# schematic_sheet1.net
KiCad netlist of a schematic drawn in Altium Designer
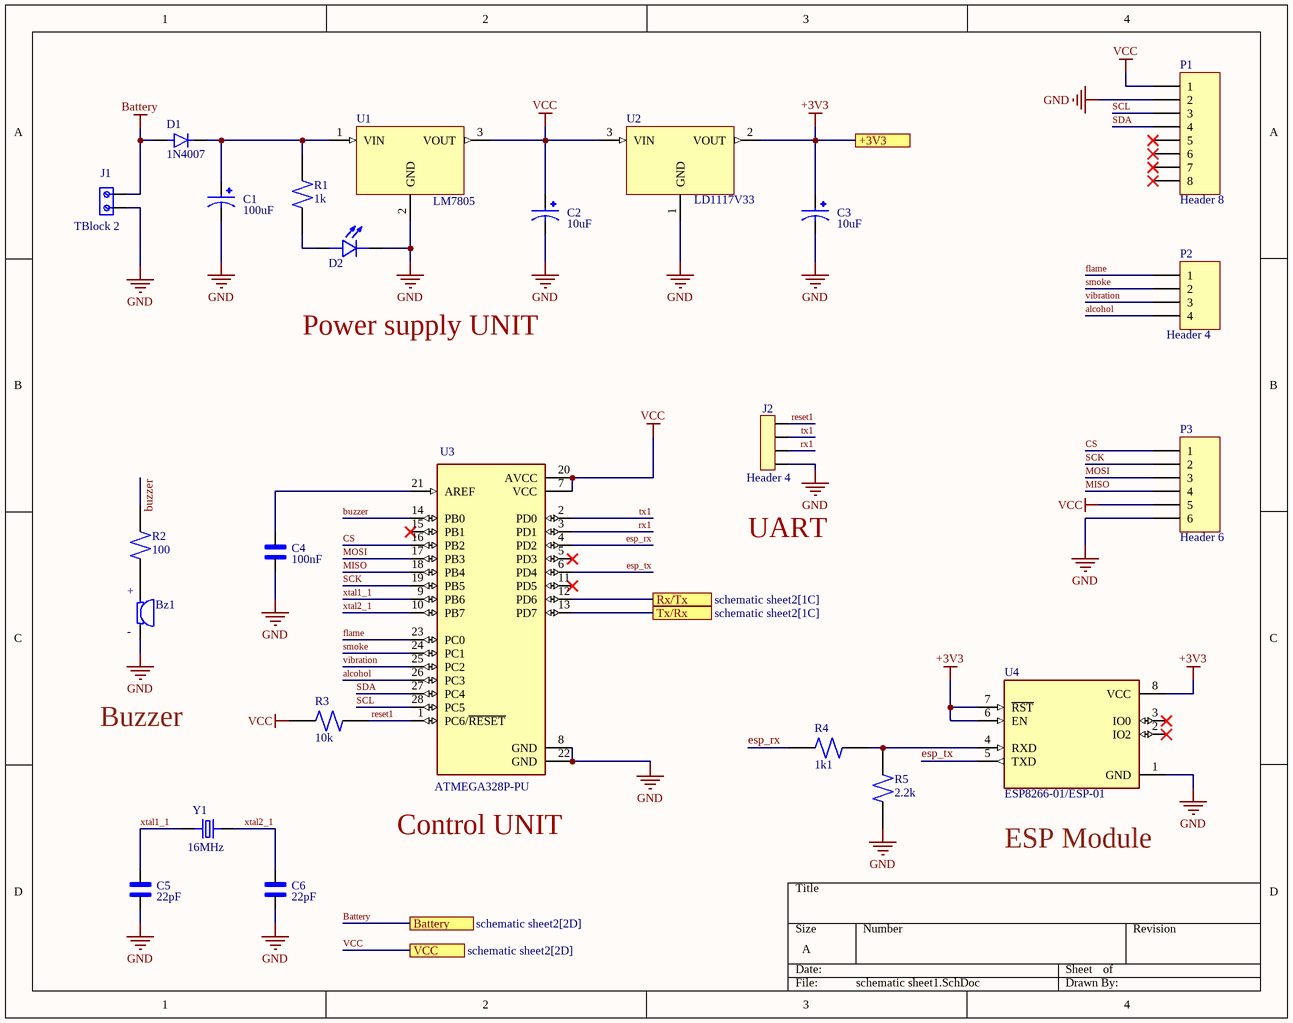
[diagram p0: schematic sheet1.SchDoc]

(export (version "E")
  (design (tool "Eeschema 10.0.6"))
  (components
    (comp (ref "Bz1")
      (value "AI-1223-TWT-12V-R")
      (footprint "XDCR_AI-1223-TWT-12V-R")
      (description "ELECTRO-MECHANICAL AUDIO INDICATOR")
      (fields (field (name "MF") "PUI Audio,"))
      (libsource (lib "Installed library") (part "Buzzer"))
    )
    (comp (ref "C1")
      (value "100uF")
      (footprint "CAPPRD500W50D500H1100")
      (description "FS-A")
      (fields (field (name "MF") "{'manufacturer': u'Panasonic'}") (field (name "MP") "EEUFS0J221B"))
      (libsource (lib "Installed library") (part "Electrolytic capacitor"))
    )
    (comp (ref "C2")
      (value "10uF")
      (footprint "CAPPRD500W50D500H1100")
      (description "FS-A")
      (fields (field (name "MF") "{'manufacturer': u'Panasonic'}") (field (name "MP") "EEUFS0J221B"))
      (libsource (lib "Installed library") (part "Electrolytic capacitor"))
    )
    (comp (ref "C3")
      (value "10uF")
      (footprint "CAPPRD500W50D500H1100")
      (description "FS-A")
      (fields (field (name "MF") "{'manufacturer': u'Panasonic'}") (field (name "MP") "EEUFS0J221B"))
      (libsource (lib "Installed library") (part "Electrolytic capacitor"))
    )
    (comp (ref "C4")
      (value "100nF")
      (footprint "CAPRB500W50L450T300H550")
      (description "2200 pF Â±10% 250V Ceramic Capacitor X7R Radial")
      (fields (field (name "DIGI-KEY_PART_NUMBER") "445-173386-1-ND") (field (name "MF") "TDK"))
      (libsource (lib "Installed library") (part "Ceramic capacitor"))
    )
    (comp (ref "C5")
      (value "22pF")
      (footprint "CAPRB500W50L450T300H550")
      (description "2200 pF Â±10% 250V Ceramic Capacitor X7R Radial")
      (fields (field (name "DIGI-KEY_PART_NUMBER") "445-173386-1-ND") (field (name "MF") "TDK"))
      (libsource (lib "Installed library") (part "Ceramic capacitor"))
    )
    (comp (ref "C6")
      (value "22pF")
      (footprint "CAPRB500W50L450T300H550")
      (description "2200 pF Â±10% 250V Ceramic Capacitor X7R Radial")
      (fields (field (name "DIGI-KEY_PART_NUMBER") "445-173386-1-ND") (field (name "MF") "TDK"))
      (libsource (lib "Installed library") (part "Ceramic capacitor"))
    )
    (comp (ref "D1")
      (value "1N4007")
      (footprint "DIOAD1060W80L520D270")
      (description "Diode Switching 1KV 1A 2-Pin DO-41")
      (libsource (lib "Components") (part "1N4007"))
    )
    (comp (ref "D2")
      (value "L08R5000Q1")
      (footprint "LEDRD254W57D500H1070")
      (description "LED, Orange, Through Hole, T-1 3/4 (5mm), 30 mA, 2.1 V, 635 nm")
      (fields (field (name "MF") "{'manufacturer': u'LED Technology'}"))
      (libsource (lib "Installed library") (part "LED"))
    )
    (comp (ref "J1")
      (value "TBlock 2")
      (footprint "691111710002")
      (description "2 Position Wire to Board Terminal Block Horizontal with Board 0.197 _5.00mm_ Through Hole")
      (fields (field (name "MP") "691111710002") (field (name "MF") "Wurth Electronics"))
      (libsource (lib "Installed library") (part "Terminal Block - 2Pins"))
    )
    (comp (ref "J2")
      (value "Header 4")
      (footprint "SULLINS_PPTC041LFBN-RC")
      (description "4 Position Header Connector Through Hole")
      (fields (field (name "MP") "PPTC041LFBN-RC") (field (name "MF") "Sullins Connector"))
      (libsource (lib "Installed library") (part "Female header - 4Pins"))
    )
    (comp (ref "P1")
      (value "Header 8")
      (footprint "HDR1X8")
      (description "Header, 8-Pin")
      (fields (field (name "PUBLISHER") "Altium Limited"))
      (libsource (lib "Miscellaneous Connectors") (part "Header 8"))
    )
    (comp (ref "P2")
      (value "Header 4")
      (footprint "HDR1X4")
      (description "Header, 4-Pin")
      (fields (field (name "PUBLISHER") "Altium Limited"))
      (libsource (lib "Miscellaneous Connectors") (part "Header 4"))
    )
    (comp (ref "P3")
      (value "Header 6")
      (footprint "HDR1X6")
      (description "Header, 6-Pin")
      (fields (field (name "PUBLISHER") "Altium Limited"))
      (libsource (lib "Miscellaneous Connectors") (part "Header 6"))
    )
    (comp (ref "R1")
      (value "1k")
      (footprint "RESAD1100W55L680D260")
      (description "(MFR-25FBF52-10K) 10,2 kOhm bei 1% 0,25W, 1/4W Durchbohrlochwiderstand Axial Metal Film")
      (fields (field (name "DIGI-KEY_PART_NUMBER") "10.2KXBK-ND") (field (name "MF") "Yageo"))
      (libsource (lib "Installed library") (part "Resistor (0.25W)"))
    )
    (comp (ref "R2")
      (value "100")
      (footprint "RESAD1100W55L680D260")
      (description "(MFR-25FBF52-10K) 10,2 kOhm bei 1% 0,25W, 1/4W Durchbohrlochwiderstand Axial Metal Film")
      (fields (field (name "DIGI-KEY_PART_NUMBER") "10.2KXBK-ND") (field (name "MF") "Yageo"))
      (libsource (lib "Installed library") (part "Resistor (0.25W)"))
    )
    (comp (ref "R3")
      (value "10k")
      (footprint "RESAD1100W55L680D260")
      (description "(MFR-25FBF52-10K) 10,2 kOhm bei 1% 0,25W, 1/4W Durchbohrlochwiderstand Axial Metal Film")
      (fields (field (name "DIGI-KEY_PART_NUMBER") "10.2KXBK-ND") (field (name "MF") "Yageo"))
      (libsource (lib "Installed library") (part "Resistor (0.25W)"))
    )
    (comp (ref "R4")
      (value "1k1")
      (footprint "RESAD1100W55L680D260")
      (description "(MFR-25FBF52-10K) 10,2 kOhm bei 1% 0,25W, 1/4W Durchbohrlochwiderstand Axial Metal Film")
      (fields (field (name "DIGI-KEY_PART_NUMBER") "10.2KXBK-ND") (field (name "MF") "Yageo"))
      (libsource (lib "Installed library") (part "Resistor (0.25W)"))
    )
    (comp (ref "R5")
      (value "2.2k")
      (footprint "RESAD1100W55L680D260")
      (description "(MFR-25FBF52-10K) 10,2 kOhm bei 1% 0,25W, 1/4W Durchbohrlochwiderstand Axial Metal Film")
      (fields (field (name "DIGI-KEY_PART_NUMBER") "10.2KXBK-ND") (field (name "MF") "Yageo"))
      (libsource (lib "Installed library") (part "Resistor (0.25W)"))
    )
    (comp (ref "U1")
      (value "LM7805")
      (footprint "TO255P1020X450X1968-3")
      (fields (field (name "MP") "LM7805CT/NOPB"))
      (libsource (lib "Voltage regulator") (part "LM78__"))
    )
    (comp (ref "U2")
      (value "LD1117V33")
      (footprint "TO255P1020X450X1968-3")
      (libsource (lib "Voltage regulator") (part "LD1117V33"))
    )
    (comp (ref "U3")
      (value "ATMEGA328P-PU")
      (footprint "DIP794W46P254L2967H457Q28B")
      (description "ATmega Series 20 MHz 32 KB Flash 2 KB SRAM 8-Bit Microcontroller - DIP-28")
      (libsource (lib "Installed library") (part "ATMEGA328P-PU"))
    )
    (comp (ref "U4")
      (value "ESP8266-01/ESP-01")
      (footprint "XCVR_ESP8266-01/ESP-01")
      (libsource (lib "Installed library") (part "ESP8266-01 Module"))
    )
    (comp (ref "Y1")
      (value "16MHz")
      (footprint "XTAL_ECS-160-20-4X")
      (description "CRYSTAL T/H")
      (fields (field (name "MF") "{'manufacturer': u'ECS Inc.'}") (field (name "MP") "ECS-160-S-4"))
      (libsource (lib "Installed library") (part "Crystal oscilator"))
    )
  )
  (nets
    (net (code "1") (name "+3V3") (class "Default")
      (node (ref "C3") (pin "P") (pinfunction "P_P") (pintype "passive"))
      (node (ref "U2") (pin "2") (pinfunction "VOUT_2") (pintype "output"))
      (node (ref "U4") (pin "6") (pinfunction "EN_6") (pintype "input"))
      (node (ref "U4") (pin "7") (pinfunction "~{RST}_7") (pintype "input"))
      (node (ref "U4") (pin "8") (pinfunction "VCC_8") (pintype "power_in"))
    )
    (net (code "2") (name "/CS") (class "Default")
      (node (ref "P3") (pin "1") (pinfunction "1_1") (pintype "passive"))
      (node (ref "U3") (pin "16") (pinfunction "PB2_16") (pintype "bidirectional"))
    )
    (net (code "3") (name "/MISO") (class "Default")
      (node (ref "P3") (pin "4") (pinfunction "4_4") (pintype "passive"))
      (node (ref "U3") (pin "18") (pinfunction "PB4_18") (pintype "bidirectional"))
    )
    (net (code "4") (name "/MOSI") (class "Default")
      (node (ref "P3") (pin "3") (pinfunction "3_3") (pintype "passive"))
      (node (ref "U3") (pin "17") (pinfunction "PB3_17") (pintype "bidirectional"))
    )
    (net (code "5") (name "/Rx{slash}Tx") (class "Default")
      (node (ref "U3") (pin "12") (pinfunction "PD6_12") (pintype "bidirectional"))
    )
    (net (code "6") (name "/SCK") (class "Default")
      (node (ref "P3") (pin "2") (pinfunction "2_2") (pintype "passive"))
      (node (ref "U3") (pin "19") (pinfunction "PB5_19") (pintype "bidirectional"))
    )
    (net (code "7") (name "/SCL") (class "Default")
      (node (ref "P1") (pin "3") (pinfunction "3_3") (pintype "passive"))
      (node (ref "U3") (pin "28") (pinfunction "PC5_28") (pintype "bidirectional"))
    )
    (net (code "8") (name "/SDA") (class "Default")
      (node (ref "P1") (pin "4") (pinfunction "4_4") (pintype "passive"))
      (node (ref "U3") (pin "27") (pinfunction "PC4_27") (pintype "bidirectional"))
    )
    (net (code "9") (name "/Tx{slash}Rx") (class "Default")
      (node (ref "U3") (pin "13") (pinfunction "PD7_13") (pintype "bidirectional"))
    )
    (net (code "10") (name "/alcohol") (class "Default")
      (node (ref "P2") (pin "4") (pinfunction "4_4") (pintype "passive"))
      (node (ref "U3") (pin "26") (pinfunction "PC3_26") (pintype "bidirectional"))
    )
    (net (code "11") (name "/buzzer") (class "Default")
      (node (ref "R2") (pin "2") (pinfunction "2_2") (pintype "passive"))
      (node (ref "U3") (pin "14") (pinfunction "PB0_14") (pintype "bidirectional"))
    )
    (net (code "12") (name "/esp_rx") (class "Default")
      (node (ref "R4") (pin "2") (pinfunction "2_2") (pintype "passive"))
      (node (ref "U3") (pin "4") (pinfunction "PD2_4") (pintype "bidirectional"))
    )
    (net (code "13") (name "/esp_tx") (class "Default")
      (node (ref "U3") (pin "6") (pinfunction "PD4_6") (pintype "bidirectional"))
      (node (ref "U4") (pin "5") (pinfunction "TXD_5") (pintype "output"))
    )
    (net (code "14") (name "/flame") (class "Default")
      (node (ref "P2") (pin "1") (pinfunction "1_1") (pintype "passive"))
      (node (ref "U3") (pin "23") (pinfunction "PC0_23") (pintype "bidirectional"))
    )
    (net (code "15") (name "/reset1") (class "Default")
      (node (ref "J2") (pin "1") (pinfunction "1_1") (pintype "passive"))
      (node (ref "R3") (pin "2") (pinfunction "2_2") (pintype "passive"))
      (node (ref "U3") (pin "1") (pinfunction "PC6/~{RESET}_1") (pintype "bidirectional"))
    )
    (net (code "16") (name "/rx1") (class "Default")
      (node (ref "J2") (pin "3") (pinfunction "3_3") (pintype "passive"))
      (node (ref "U3") (pin "3") (pinfunction "PD1_3") (pintype "bidirectional"))
    )
    (net (code "17") (name "/smoke") (class "Default")
      (node (ref "P2") (pin "2") (pinfunction "2_2") (pintype "passive"))
      (node (ref "U3") (pin "24") (pinfunction "PC1_24") (pintype "bidirectional"))
    )
    (net (code "18") (name "/tx1") (class "Default")
      (node (ref "J2") (pin "2") (pinfunction "2_2") (pintype "passive"))
      (node (ref "U3") (pin "2") (pinfunction "PD0_2") (pintype "bidirectional"))
    )
    (net (code "19") (name "/vibration") (class "Default")
      (node (ref "P2") (pin "3") (pinfunction "3_3") (pintype "passive"))
      (node (ref "U3") (pin "25") (pinfunction "PC2_25") (pintype "bidirectional"))
    )
    (net (code "20") (name "/xtal1_1") (class "Default")
      (node (ref "C5") (pin "1") (pinfunction "1_1") (pintype "passive"))
      (node (ref "U3") (pin "9") (pinfunction "PB6_9") (pintype "bidirectional"))
      (node (ref "Y1") (pin "1") (pinfunction "1_1") (pintype "passive"))
    )
    (net (code "21") (name "/xtal2_1") (class "Default")
      (node (ref "C6") (pin "1") (pinfunction "1_1") (pintype "passive"))
      (node (ref "U3") (pin "10") (pinfunction "PB7_10") (pintype "bidirectional"))
      (node (ref "Y1") (pin "2") (pinfunction "2_2") (pintype "passive"))
    )
    (net (code "22") (name "Battery") (class "Default")
      (node (ref "D1") (pin "A") (pinfunction "A_A") (pintype "passive"))
      (node (ref "J1") (pin "2") (pinfunction "2_2") (pintype "passive"))
    )
    (net (code "23") (name "GND") (class "Default")
      (node (ref "Bz1") (pin "N") (pinfunction "NEG_N") (pintype "passive"))
      (node (ref "C1") (pin "N") (pinfunction "N_N") (pintype "passive"))
      (node (ref "C2") (pin "N") (pinfunction "N_N") (pintype "passive"))
      (node (ref "C3") (pin "N") (pinfunction "N_N") (pintype "passive"))
      (node (ref "C4") (pin "2") (pinfunction "2_2") (pintype "passive"))
      (node (ref "C5") (pin "2") (pinfunction "2_2") (pintype "passive"))
      (node (ref "C6") (pin "2") (pinfunction "2_2") (pintype "passive"))
      (node (ref "D2") (pin "C") (pinfunction "C_C") (pintype "passive"))
      (node (ref "J1") (pin "1") (pinfunction "1_1") (pintype "passive"))
      (node (ref "J2") (pin "4") (pinfunction "4_4") (pintype "passive"))
      (node (ref "P1") (pin "2") (pinfunction "2_2") (pintype "passive"))
      (node (ref "P3") (pin "6") (pinfunction "6_6") (pintype "passive"))
      (node (ref "R5") (pin "1") (pinfunction "1_1") (pintype "passive"))
      (node (ref "U1") (pin "2") (pinfunction "GND_2") (pintype "passive"))
      (node (ref "U2") (pin "1") (pinfunction "GND_1") (pintype "passive"))
      (node (ref "U3") (pin "22") (pinfunction "GND_22") (pintype "power_in"))
      (node (ref "U3") (pin "8") (pinfunction "GND_8") (pintype "power_in"))
      (node (ref "U4") (pin "1") (pinfunction "GND_1") (pintype "power_in"))
    )
    (net (code "24") (name "Net-(Bz1-POS)") (class "Default")
      (node (ref "Bz1") (pin "P") (pinfunction "POS_P") (pintype "passive"))
      (node (ref "R2") (pin "1") (pinfunction "1_1") (pintype "passive"))
    )
    (net (code "25") (name "Net-(D2-PadA)") (class "Default")
      (node (ref "D2") (pin "A") (pinfunction "A_A") (pintype "passive"))
      (node (ref "R1") (pin "2") (pinfunction "2_2") (pintype "passive"))
    )
    (net (code "26") (name "Net-(U1-VIN)") (class "Default")
      (node (ref "C1") (pin "P") (pinfunction "P_P") (pintype "passive"))
      (node (ref "D1") (pin "C") (pinfunction "C_C") (pintype "passive"))
      (node (ref "R1") (pin "1") (pinfunction "1_1") (pintype "passive"))
      (node (ref "U1") (pin "1") (pinfunction "VIN_1") (pintype "input"))
    )
    (net (code "27") (name "Net-(U3-AREF)") (class "Default")
      (node (ref "C4") (pin "1") (pinfunction "1_1") (pintype "passive"))
      (node (ref "U3") (pin "21") (pinfunction "AREF_21") (pintype "input"))
    )
    (net (code "28") (name "Net-(U4-RXD)") (class "Default")
      (node (ref "R4") (pin "1") (pinfunction "1_1") (pintype "passive"))
      (node (ref "R5") (pin "2") (pinfunction "2_2") (pintype "passive"))
      (node (ref "U4") (pin "4") (pinfunction "RXD_4") (pintype "input"))
    )
    (net (code "29") (name "VCC") (class "Default")
      (node (ref "C2") (pin "P") (pinfunction "P_P") (pintype "passive"))
      (node (ref "P1") (pin "1") (pinfunction "1_1") (pintype "passive"))
      (node (ref "P3") (pin "5") (pinfunction "5_5") (pintype "passive"))
      (node (ref "R3") (pin "1") (pinfunction "1_1") (pintype "passive"))
      (node (ref "U1") (pin "3") (pinfunction "VOUT_3") (pintype "output"))
      (node (ref "U2") (pin "3") (pinfunction "VIN_3") (pintype "input"))
      (node (ref "U3") (pin "20") (pinfunction "AVCC_20") (pintype "power_in"))
      (node (ref "U3") (pin "7") (pinfunction "VCC_7") (pintype "power_in"))
    )
    (net (code "30") (name "unconnected-(P1-Pad5)") (class "Default")
      (node (ref "P1") (pin "5") (pinfunction "5_5") (pintype "passive+no_connect"))
    )
    (net (code "31") (name "unconnected-(P1-Pad6)") (class "Default")
      (node (ref "P1") (pin "6") (pinfunction "6_6") (pintype "passive+no_connect"))
    )
    (net (code "32") (name "unconnected-(P1-Pad7)") (class "Default")
      (node (ref "P1") (pin "7") (pinfunction "7_7") (pintype "passive+no_connect"))
    )
    (net (code "33") (name "unconnected-(P1-Pad8)") (class "Default")
      (node (ref "P1") (pin "8") (pinfunction "8_8") (pintype "passive+no_connect"))
    )
    (net (code "34") (name "unconnected-(U3-PB1-Pad15)") (class "Default")
      (node (ref "U3") (pin "15") (pinfunction "PB1_15") (pintype "bidirectional+no_connect"))
    )
    (net (code "35") (name "unconnected-(U3-PD3-Pad5)") (class "Default")
      (node (ref "U3") (pin "5") (pinfunction "PD3_5") (pintype "bidirectional+no_connect"))
    )
    (net (code "36") (name "unconnected-(U3-PD5-Pad11)") (class "Default")
      (node (ref "U3") (pin "11") (pinfunction "PD5_11") (pintype "bidirectional+no_connect"))
    )
    (net (code "37") (name "unconnected-(U4-IO0-Pad3)") (class "Default")
      (node (ref "U4") (pin "3") (pinfunction "IO0_3") (pintype "bidirectional+no_connect"))
    )
    (net (code "38") (name "unconnected-(U4-IO2-Pad2)") (class "Default")
      (node (ref "U4") (pin "2") (pinfunction "IO2_2") (pintype "bidirectional+no_connect"))
    )
  )
)
